# nf10_addon.net
KiCad netlist of a schematic drawn in Altium Designer
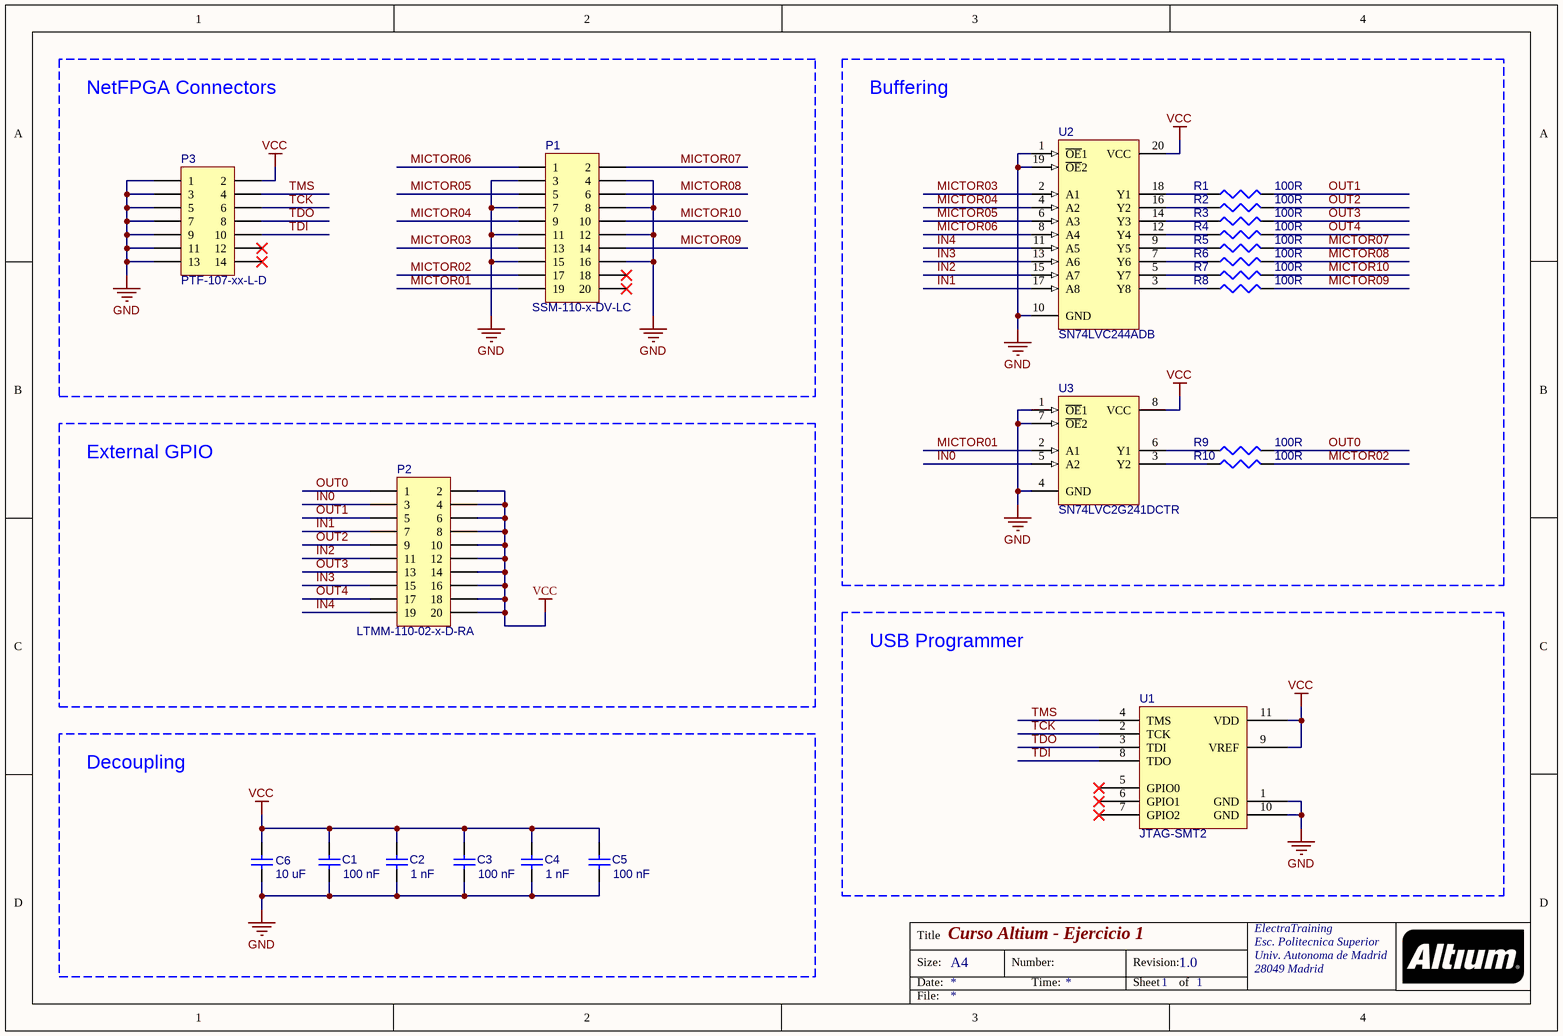
[diagram p0: nf10_addon.SchDoc]

(export (version "E")
  (design (tool "Eeschema 10.0.6"))
  (components
    (comp (ref "C1")
      (value "100 nF")
      (footprint "CAPC0603(1608)100_N")
      (description "Capacitor")
      (fields (field (name "Comment") "Cap") (field (name "PUBLISHER") "Altium Limited"))
      (libsource (lib "Miscellaneous Devices") (part "Cap"))
    )
    (comp (ref "C2")
      (value "1 nF")
      (footprint "CAPC0603(1608)100_N")
      (description "Capacitor")
      (fields (field (name "Comment") "Cap") (field (name "PUBLISHER") "Altium Limited"))
      (libsource (lib "Miscellaneous Devices") (part "Cap"))
    )
    (comp (ref "C3")
      (value "100 nF")
      (footprint "CAPC0603(1608)100_N")
      (description "Capacitor")
      (fields (field (name "Comment") "Cap") (field (name "PUBLISHER") "Altium Limited"))
      (libsource (lib "Miscellaneous Devices") (part "Cap"))
    )
    (comp (ref "C4")
      (value "1 nF")
      (footprint "CAPC0603(1608)100_N")
      (description "Capacitor")
      (fields (field (name "Comment") "Cap") (field (name "PUBLISHER") "Altium Limited"))
      (libsource (lib "Miscellaneous Devices") (part "Cap"))
    )
    (comp (ref "C5")
      (value "100 nF")
      (footprint "CAPC0603(1608)100_N")
      (description "Capacitor")
      (fields (field (name "Comment") "Cap") (field (name "PUBLISHER") "Altium Limited"))
      (libsource (lib "Miscellaneous Devices") (part "Cap"))
    )
    (comp (ref "C6")
      (value "10 uF")
      (footprint "CAPC1206(3216)100_N")
      (description "Capacitor")
      (fields (field (name "Comment") "Cap") (field (name "PUBLISHER") "Altium Limited"))
      (libsource (lib "Miscellaneous Devices") (part "Cap"))
    )
    (comp (ref "P1")
      (value "SSM-110-x-DV-LC")
      (footprint "SSM-110-X-DV-LC")
      (description "Samtec SSM-110-x-DV-LC")
      (fields (field (name "PUBLISHER") "Altium Limited"))
      (libsource (lib "nf10_addon") (part "SSM-110-x-DV-LC"))
    )
    (comp (ref "P2")
      (value "LTMM-110-02-x-D-RA")
      (footprint "LTMM-110-02-X-D-RA")
      (description "Samtec LTMM-110-02-x-D-RA")
      (fields (field (name "PUBLISHER") "Altium Limited"))
      (libsource (lib "nf10_addon") (part "LTMM-110-02-x-D-RA"))
    )
    (comp (ref "P3")
      (value "PTF-107-xx-L-D")
      (footprint "PTF-107-XX-L-D")
      (description "Samtec PTF-107-xx-L-D")
      (fields (field (name "PUBLISHER") "Altium Limited"))
      (libsource (lib "nf10_addon") (part "PTF-107-xx-L-D"))
    )
    (comp (ref "R1")
      (value "100R")
      (footprint "RESC0603(1608)_N")
      (description "Resistor")
      (fields (field (name "Comment") "Res3") (field (name "PUBLISHER") "Altium Limited"))
      (libsource (lib "Miscellaneous Devices") (part "Res3"))
    )
    (comp (ref "R2")
      (value "100R")
      (footprint "RESC0603(1608)_N")
      (description "Resistor")
      (fields (field (name "Comment") "Res3") (field (name "PUBLISHER") "Altium Limited"))
      (libsource (lib "Miscellaneous Devices") (part "Res3"))
    )
    (comp (ref "R3")
      (value "100R")
      (footprint "RESC0603(1608)_N")
      (description "Resistor")
      (fields (field (name "Comment") "Res3") (field (name "PUBLISHER") "Altium Limited"))
      (libsource (lib "Miscellaneous Devices") (part "Res3"))
    )
    (comp (ref "R4")
      (value "100R")
      (footprint "RESC0603(1608)_N")
      (description "Resistor")
      (fields (field (name "Comment") "Res3") (field (name "PUBLISHER") "Altium Limited"))
      (libsource (lib "Miscellaneous Devices") (part "Res3"))
    )
    (comp (ref "R5")
      (value "100R")
      (footprint "RESC0603(1608)_N")
      (description "Resistor")
      (fields (field (name "Comment") "Res3") (field (name "PUBLISHER") "Altium Limited"))
      (libsource (lib "Miscellaneous Devices") (part "Res3"))
    )
    (comp (ref "R6")
      (value "100R")
      (footprint "RESC0603(1608)_N")
      (description "Resistor")
      (fields (field (name "Comment") "Res3") (field (name "PUBLISHER") "Altium Limited"))
      (libsource (lib "Miscellaneous Devices") (part "Res3"))
    )
    (comp (ref "R7")
      (value "100R")
      (footprint "RESC0603(1608)_N")
      (description "Resistor")
      (fields (field (name "Comment") "Res3") (field (name "PUBLISHER") "Altium Limited"))
      (libsource (lib "Miscellaneous Devices") (part "Res3"))
    )
    (comp (ref "R8")
      (value "100R")
      (footprint "RESC0603(1608)_N")
      (description "Resistor")
      (fields (field (name "Comment") "Res3") (field (name "PUBLISHER") "Altium Limited"))
      (libsource (lib "Miscellaneous Devices") (part "Res3"))
    )
    (comp (ref "R9")
      (value "100R")
      (footprint "RESC0603(1608)_N")
      (description "Resistor")
      (fields (field (name "Comment") "Res3") (field (name "PUBLISHER") "Altium Limited"))
      (libsource (lib "Miscellaneous Devices") (part "Res3"))
    )
    (comp (ref "R10")
      (value "100R")
      (footprint "RESC0603(1608)_N")
      (description "Resistor")
      (fields (field (name "Comment") "Res3") (field (name "PUBLISHER") "Altium Limited"))
      (libsource (lib "Miscellaneous Devices") (part "Res3"))
    )
    (comp (ref "U1")
      (value "JTAG-SMT2")
      (footprint "JTAG-SMT2")
      (libsource (lib "NetFPGA10G_Addon") (part "JTAG_SMT2"))
    )
    (comp (ref "U2")
      (value "SN74LVC244ADB")
      (footprint "DB020_N")
      (description "Octal Buffer/Driver with 3-State Outputs")
      (fields (field (name "PUBLISHER") "Altium Limited"))
      (libsource (lib "TI Logic Buffer Line Driver") (part "SN74LVC244ADB"))
    )
    (comp (ref "U3")
      (value "SN74LVC2G241DCTR")
      (footprint "DCT08_N")
      (description "Quadruple Bus Buffer Gate with 3- State Outputs")
      (fields (field (name "PUBLISHER") "Altium Limited"))
      (libsource (lib "nf10_addon") (part "SN74LVC2G241DCTR"))
    )
  )
  (nets
    (net (code "1") (name "/IN0") (class "Default")
      (node (ref "P2") (pin "3") (pinfunction "3_3") (pintype "passive"))
      (node (ref "U3") (pin "5") (pinfunction "A2_5") (pintype "input"))
    )
    (net (code "2") (name "/IN1") (class "Default")
      (node (ref "P2") (pin "7") (pinfunction "7_7") (pintype "passive"))
      (node (ref "U2") (pin "17") (pinfunction "A8_17") (pintype "input"))
    )
    (net (code "3") (name "/IN2") (class "Default")
      (node (ref "P2") (pin "11") (pinfunction "11_11") (pintype "passive"))
      (node (ref "U2") (pin "15") (pinfunction "A7_15") (pintype "input"))
    )
    (net (code "4") (name "/IN3") (class "Default")
      (node (ref "P2") (pin "15") (pinfunction "15_15") (pintype "passive"))
      (node (ref "U2") (pin "13") (pinfunction "A6_13") (pintype "input"))
    )
    (net (code "5") (name "/IN4") (class "Default")
      (node (ref "P2") (pin "19") (pinfunction "19_19") (pintype "passive"))
      (node (ref "U2") (pin "11") (pinfunction "A5_11") (pintype "input"))
    )
    (net (code "6") (name "/MICTOR01") (class "Default")
      (node (ref "P1") (pin "19") (pinfunction "19_19") (pintype "passive"))
      (node (ref "U3") (pin "2") (pinfunction "A1_2") (pintype "input"))
    )
    (net (code "7") (name "/MICTOR02") (class "Default")
      (node (ref "P1") (pin "17") (pinfunction "17_17") (pintype "passive"))
      (node (ref "R10") (pin "2") (pinfunction "2_2") (pintype "passive"))
    )
    (net (code "8") (name "/MICTOR03") (class "Default")
      (node (ref "P1") (pin "13") (pinfunction "13_13") (pintype "passive"))
      (node (ref "U2") (pin "2") (pinfunction "A1_2") (pintype "input"))
    )
    (net (code "9") (name "/MICTOR04") (class "Default")
      (node (ref "P1") (pin "9") (pinfunction "9_9") (pintype "passive"))
      (node (ref "U2") (pin "4") (pinfunction "A2_4") (pintype "input"))
    )
    (net (code "10") (name "/MICTOR05") (class "Default")
      (node (ref "P1") (pin "5") (pinfunction "5_5") (pintype "passive"))
      (node (ref "U2") (pin "6") (pinfunction "A3_6") (pintype "input"))
    )
    (net (code "11") (name "/MICTOR06") (class "Default")
      (node (ref "P1") (pin "1") (pinfunction "1_1") (pintype "passive"))
      (node (ref "U2") (pin "8") (pinfunction "A4_8") (pintype "input"))
    )
    (net (code "12") (name "/MICTOR07") (class "Default")
      (node (ref "P1") (pin "2") (pinfunction "2_2") (pintype "passive"))
      (node (ref "R5") (pin "2") (pinfunction "2_2") (pintype "passive"))
    )
    (net (code "13") (name "/MICTOR08") (class "Default")
      (node (ref "P1") (pin "6") (pinfunction "6_6") (pintype "passive"))
      (node (ref "R6") (pin "2") (pinfunction "2_2") (pintype "passive"))
    )
    (net (code "14") (name "/MICTOR09") (class "Default")
      (node (ref "P1") (pin "14") (pinfunction "14_14") (pintype "passive"))
      (node (ref "R8") (pin "2") (pinfunction "2_2") (pintype "passive"))
    )
    (net (code "15") (name "/MICTOR10") (class "Default")
      (node (ref "P1") (pin "10") (pinfunction "10_10") (pintype "passive"))
      (node (ref "R7") (pin "2") (pinfunction "2_2") (pintype "passive"))
    )
    (net (code "16") (name "/OUT0") (class "Default")
      (node (ref "P2") (pin "1") (pinfunction "1_1") (pintype "passive"))
      (node (ref "R9") (pin "2") (pinfunction "2_2") (pintype "passive"))
    )
    (net (code "17") (name "/OUT1") (class "Default")
      (node (ref "P2") (pin "5") (pinfunction "5_5") (pintype "passive"))
      (node (ref "R1") (pin "2") (pinfunction "2_2") (pintype "passive"))
    )
    (net (code "18") (name "/OUT2") (class "Default")
      (node (ref "P2") (pin "9") (pinfunction "9_9") (pintype "passive"))
      (node (ref "R2") (pin "2") (pinfunction "2_2") (pintype "passive"))
    )
    (net (code "19") (name "/OUT3") (class "Default")
      (node (ref "P2") (pin "13") (pinfunction "13_13") (pintype "passive"))
      (node (ref "R3") (pin "2") (pinfunction "2_2") (pintype "passive"))
    )
    (net (code "20") (name "/OUT4") (class "Default")
      (node (ref "P2") (pin "17") (pinfunction "17_17") (pintype "passive"))
      (node (ref "R4") (pin "2") (pinfunction "2_2") (pintype "passive"))
    )
    (net (code "21") (name "/TCK") (class "Default")
      (node (ref "P3") (pin "6") (pinfunction "6_6") (pintype "passive"))
      (node (ref "U1") (pin "2") (pinfunction "TCK_2") (pintype "passive"))
    )
    (net (code "22") (name "/TDI") (class "Default")
      (node (ref "P3") (pin "10") (pinfunction "10_10") (pintype "passive"))
      (node (ref "U1") (pin "8") (pinfunction "TDO_8") (pintype "passive"))
    )
    (net (code "23") (name "/TDO") (class "Default")
      (node (ref "P3") (pin "8") (pinfunction "8_8") (pintype "passive"))
      (node (ref "U1") (pin "3") (pinfunction "TDI_3") (pintype "passive"))
    )
    (net (code "24") (name "/TMS") (class "Default")
      (node (ref "P3") (pin "4") (pinfunction "4_4") (pintype "passive"))
      (node (ref "U1") (pin "4") (pinfunction "TMS_4") (pintype "passive"))
    )
    (net (code "25") (name "GND") (class "Default")
      (node (ref "C1") (pin "1") (pinfunction "1_1") (pintype "passive"))
      (node (ref "C2") (pin "1") (pinfunction "1_1") (pintype "passive"))
      (node (ref "C3") (pin "1") (pinfunction "1_1") (pintype "passive"))
      (node (ref "C4") (pin "1") (pinfunction "1_1") (pintype "passive"))
      (node (ref "C5") (pin "1") (pinfunction "1_1") (pintype "passive"))
      (node (ref "C6") (pin "1") (pinfunction "1_1") (pintype "passive"))
      (node (ref "P1") (pin "11") (pinfunction "11_11") (pintype "passive"))
      (node (ref "P1") (pin "12") (pinfunction "12_12") (pintype "passive"))
      (node (ref "P1") (pin "15") (pinfunction "15_15") (pintype "passive"))
      (node (ref "P1") (pin "16") (pinfunction "16_16") (pintype "passive"))
      (node (ref "P1") (pin "3") (pinfunction "3_3") (pintype "passive"))
      (node (ref "P1") (pin "4") (pinfunction "4_4") (pintype "passive"))
      (node (ref "P1") (pin "7") (pinfunction "7_7") (pintype "passive"))
      (node (ref "P1") (pin "8") (pinfunction "8_8") (pintype "passive"))
      (node (ref "P3") (pin "1") (pinfunction "1_1") (pintype "passive"))
      (node (ref "P3") (pin "11") (pinfunction "11_11") (pintype "passive"))
      (node (ref "P3") (pin "13") (pinfunction "13_13") (pintype "passive"))
      (node (ref "P3") (pin "3") (pinfunction "3_3") (pintype "passive"))
      (node (ref "P3") (pin "5") (pinfunction "5_5") (pintype "passive"))
      (node (ref "P3") (pin "7") (pinfunction "7_7") (pintype "passive"))
      (node (ref "P3") (pin "9") (pinfunction "9_9") (pintype "passive"))
      (node (ref "U1") (pin "1") (pinfunction "GND_1") (pintype "passive"))
      (node (ref "U1") (pin "10") (pinfunction "GND_10") (pintype "passive"))
      (node (ref "U2") (pin "1") (pinfunction "~{OE}1_1") (pintype "input"))
      (node (ref "U2") (pin "10") (pinfunction "GND_10") (pintype "power_in"))
      (node (ref "U2") (pin "19") (pinfunction "~{OE}2_19") (pintype "input"))
      (node (ref "U3") (pin "1") (pinfunction "~{OE}1_1") (pintype "input"))
      (node (ref "U3") (pin "4") (pinfunction "GND_4") (pintype "power_in"))
      (node (ref "U3") (pin "7") (pinfunction "~{OE}2_7") (pintype "input"))
    )
    (net (code "26") (name "Net-(U2-Y1)") (class "Default")
      (node (ref "R1") (pin "1") (pinfunction "1_1") (pintype "passive"))
      (node (ref "U2") (pin "18") (pinfunction "Y1_18") (pintype "tri_state"))
    )
    (net (code "27") (name "Net-(U2-Y2)") (class "Default")
      (node (ref "R2") (pin "1") (pinfunction "1_1") (pintype "passive"))
      (node (ref "U2") (pin "16") (pinfunction "Y2_16") (pintype "tri_state"))
    )
    (net (code "28") (name "Net-(U2-Y3)") (class "Default")
      (node (ref "R3") (pin "1") (pinfunction "1_1") (pintype "passive"))
      (node (ref "U2") (pin "14") (pinfunction "Y3_14") (pintype "tri_state"))
    )
    (net (code "29") (name "Net-(U2-Y4)") (class "Default")
      (node (ref "R4") (pin "1") (pinfunction "1_1") (pintype "passive"))
      (node (ref "U2") (pin "12") (pinfunction "Y4_12") (pintype "tri_state"))
    )
    (net (code "30") (name "Net-(U2-Y5)") (class "Default")
      (node (ref "R5") (pin "1") (pinfunction "1_1") (pintype "passive"))
      (node (ref "U2") (pin "9") (pinfunction "Y5_9") (pintype "tri_state"))
    )
    (net (code "31") (name "Net-(U2-Y6)") (class "Default")
      (node (ref "R6") (pin "1") (pinfunction "1_1") (pintype "passive"))
      (node (ref "U2") (pin "7") (pinfunction "Y6_7") (pintype "tri_state"))
    )
    (net (code "32") (name "Net-(U2-Y7)") (class "Default")
      (node (ref "R7") (pin "1") (pinfunction "1_1") (pintype "passive"))
      (node (ref "U2") (pin "5") (pinfunction "Y7_5") (pintype "tri_state"))
    )
    (net (code "33") (name "Net-(U2-Y8)") (class "Default")
      (node (ref "R8") (pin "1") (pinfunction "1_1") (pintype "passive"))
      (node (ref "U2") (pin "3") (pinfunction "Y8_3") (pintype "tri_state"))
    )
    (net (code "34") (name "Net-(U3-Y1)") (class "Default")
      (node (ref "R9") (pin "1") (pinfunction "1_1") (pintype "passive"))
      (node (ref "U3") (pin "6") (pinfunction "Y1_6") (pintype "tri_state"))
    )
    (net (code "35") (name "Net-(U3-Y2)") (class "Default")
      (node (ref "R10") (pin "1") (pinfunction "1_1") (pintype "passive"))
      (node (ref "U3") (pin "3") (pinfunction "Y2_3") (pintype "tri_state"))
    )
    (net (code "36") (name "VCC") (class "Default")
      (node (ref "C1") (pin "2") (pinfunction "2_2") (pintype "passive"))
      (node (ref "C2") (pin "2") (pinfunction "2_2") (pintype "passive"))
      (node (ref "C3") (pin "2") (pinfunction "2_2") (pintype "passive"))
      (node (ref "C4") (pin "2") (pinfunction "2_2") (pintype "passive"))
      (node (ref "C5") (pin "2") (pinfunction "2_2") (pintype "passive"))
      (node (ref "C6") (pin "2") (pinfunction "2_2") (pintype "passive"))
      (node (ref "P2") (pin "10") (pinfunction "10_10") (pintype "passive"))
      (node (ref "P2") (pin "12") (pinfunction "12_12") (pintype "passive"))
      (node (ref "P2") (pin "14") (pinfunction "14_14") (pintype "passive"))
      (node (ref "P2") (pin "16") (pinfunction "16_16") (pintype "passive"))
      (node (ref "P2") (pin "18") (pinfunction "18_18") (pintype "passive"))
      (node (ref "P2") (pin "2") (pinfunction "2_2") (pintype "passive"))
      (node (ref "P2") (pin "20") (pinfunction "20_20") (pintype "passive"))
      (node (ref "P2") (pin "4") (pinfunction "4_4") (pintype "passive"))
      (node (ref "P2") (pin "6") (pinfunction "6_6") (pintype "passive"))
      (node (ref "P2") (pin "8") (pinfunction "8_8") (pintype "passive"))
      (node (ref "P3") (pin "2") (pinfunction "2_2") (pintype "passive"))
      (node (ref "U1") (pin "11") (pinfunction "VDD_11") (pintype "passive"))
      (node (ref "U1") (pin "9") (pinfunction "VREF_9") (pintype "passive"))
      (node (ref "U2") (pin "20") (pinfunction "VCC_20") (pintype "power_in"))
      (node (ref "U3") (pin "8") (pinfunction "VCC_8") (pintype "power_in"))
    )
    (net (code "37") (name "unconnected-(P1-Pad18)") (class "Default")
      (node (ref "P1") (pin "18") (pinfunction "18_18") (pintype "passive+no_connect"))
    )
    (net (code "38") (name "unconnected-(P1-Pad20)") (class "Default")
      (node (ref "P1") (pin "20") (pinfunction "20_20") (pintype "passive+no_connect"))
    )
    (net (code "39") (name "unconnected-(P3-Pad12)") (class "Default")
      (node (ref "P3") (pin "12") (pinfunction "12_12") (pintype "passive+no_connect"))
    )
    (net (code "40") (name "unconnected-(P3-Pad14)") (class "Default")
      (node (ref "P3") (pin "14") (pinfunction "14_14") (pintype "passive+no_connect"))
    )
    (net (code "41") (name "unconnected-(U1-GPIO0-Pad5)") (class "Default")
      (node (ref "U1") (pin "5") (pinfunction "GPIO0_5") (pintype "passive+no_connect"))
    )
    (net (code "42") (name "unconnected-(U1-GPIO1-Pad6)") (class "Default")
      (node (ref "U1") (pin "6") (pinfunction "GPIO1_6") (pintype "passive+no_connect"))
    )
    (net (code "43") (name "unconnected-(U1-GPIO2-Pad7)") (class "Default")
      (node (ref "U1") (pin "7") (pinfunction "GPIO2_7") (pintype "passive+no_connect"))
    )
  )
)
